# Output.net
KiCad netlist of a schematic drawn in Altium Designer
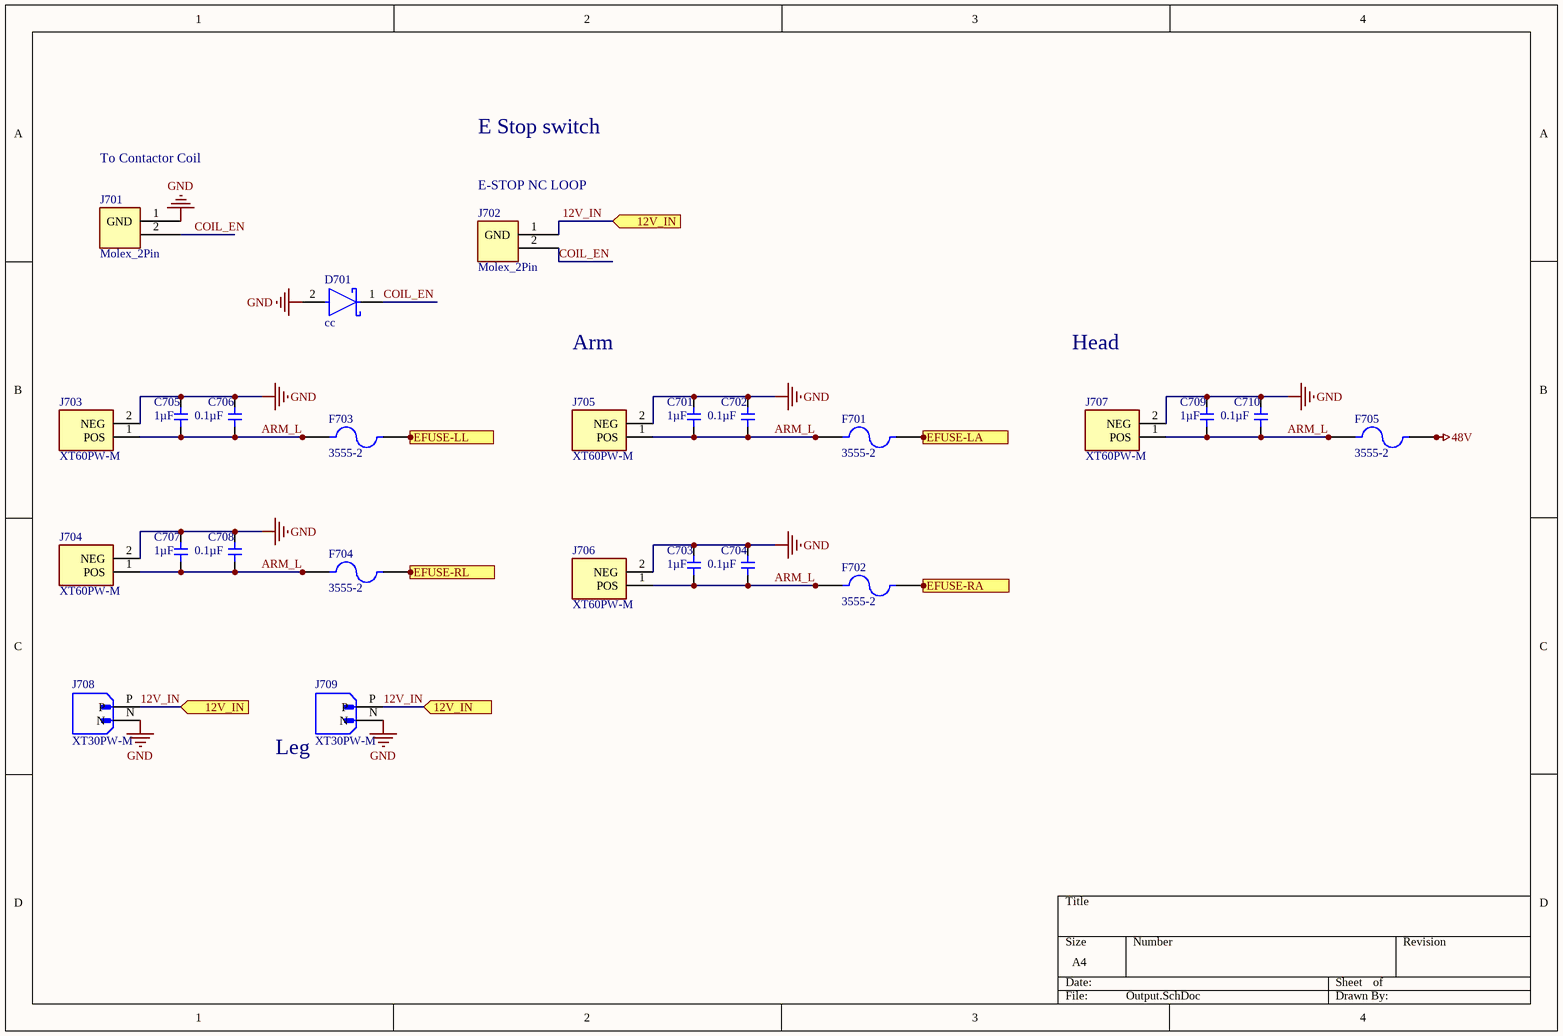
[diagram p0: Output.SchDoc]

(export (version "E")
  (design (tool "Eeschema 10.0.6"))
  (components
    (comp (ref "C701")
      (value "non-polar_Capacitor")
      (footprint "0805")
      (description "SMD type ceramic capacitor")
      (fields
        (field (name "VOLTAGE") "100V")
        (field (name "CAPACITANCE") "1µF")
        (field (name "SOURCE") "robit_passive.SchLib")
      )
      (libsource (lib "robit circuit") (part "Capacitor"))
    )
    (comp (ref "C702")
      (value "non-polar_Capacitor")
      (footprint "0603")
      (description "SMD type ceramic capacitor")
      (fields
        (field (name "VOLTAGE") "100V")
        (field (name "CAPACITANCE") "0.1µF")
        (field (name "SOURCE") "robit_passive.SchLib")
      )
      (libsource (lib "robit circuit") (part "Capacitor"))
    )
    (comp (ref "C703")
      (value "non-polar_Capacitor")
      (footprint "0805")
      (description "SMD type ceramic capacitor")
      (fields
        (field (name "VOLTAGE") "100V")
        (field (name "CAPACITANCE") "1µF")
        (field (name "SOURCE") "robit_passive.SchLib")
      )
      (libsource (lib "robit circuit") (part "Capacitor"))
    )
    (comp (ref "C704")
      (value "non-polar_Capacitor")
      (footprint "0603")
      (description "SMD type ceramic capacitor")
      (fields
        (field (name "VOLTAGE") "100V")
        (field (name "CAPACITANCE") "0.1µF")
        (field (name "SOURCE") "robit_passive.SchLib")
      )
      (libsource (lib "robit circuit") (part "Capacitor"))
    )
    (comp (ref "C705")
      (value "non-polar_Capacitor")
      (footprint "0805")
      (description "SMD type ceramic capacitor")
      (fields
        (field (name "VOLTAGE") "100V")
        (field (name "CAPACITANCE") "1µF")
        (field (name "SOURCE") "robit_passive.SchLib")
      )
      (libsource (lib "robit circuit") (part "Capacitor"))
    )
    (comp (ref "C706")
      (value "non-polar_Capacitor")
      (footprint "0603")
      (description "SMD type ceramic capacitor")
      (fields
        (field (name "VOLTAGE") "100V")
        (field (name "CAPACITANCE") "0.1µF")
        (field (name "SOURCE") "robit_passive.SchLib")
      )
      (libsource (lib "robit circuit") (part "Capacitor"))
    )
    (comp (ref "C707")
      (value "non-polar_Capacitor")
      (footprint "0805")
      (description "SMD type ceramic capacitor")
      (fields
        (field (name "VOLTAGE") "100V")
        (field (name "CAPACITANCE") "1µF")
        (field (name "SOURCE") "robit_passive.SchLib")
      )
      (libsource (lib "robit circuit") (part "Capacitor"))
    )
    (comp (ref "C708")
      (value "non-polar_Capacitor")
      (footprint "0603")
      (description "SMD type ceramic capacitor")
      (fields
        (field (name "VOLTAGE") "100V")
        (field (name "CAPACITANCE") "0.1µF")
        (field (name "SOURCE") "robit_passive.SchLib")
      )
      (libsource (lib "robit circuit") (part "Capacitor"))
    )
    (comp (ref "C709")
      (value "non-polar_Capacitor")
      (footprint "0805")
      (description "SMD type ceramic capacitor")
      (fields
        (field (name "VOLTAGE") "100V")
        (field (name "CAPACITANCE") "1µF")
        (field (name "SOURCE") "robit_passive.SchLib")
      )
      (libsource (lib "robit circuit") (part "Capacitor"))
    )
    (comp (ref "C710")
      (value "non-polar_Capacitor")
      (footprint "0603")
      (description "SMD type ceramic capacitor")
      (fields
        (field (name "VOLTAGE") "100V")
        (field (name "CAPACITANCE") "0.1µF")
        (field (name "SOURCE") "robit_passive.SchLib")
      )
      (libsource (lib "robit circuit") (part "Capacitor"))
    )
    (comp (ref "D701")
      (value "cc")
      (footprint "FP-403A-03-MFG")
      (description "Rectifier Diode, Schottky, 1 Phase, 1 Element, 5A, 100V V(RRM), Silicon")
      (libsource (lib "robit circuit") (part "1d6ec82d83fb6aee721767c19dac4b9"))
    )
    (comp (ref "F701")
      (value "3555-2")
      (footprint "FUSE_3555-2")
      (fields (field (name "MF") "Keystone Electronics"))
      (libsource (lib "3555-2 (1)") (part "3555-2"))
    )
    (comp (ref "F702")
      (value "3555-2")
      (footprint "FUSE_3555-2")
      (fields (field (name "MF") "Keystone Electronics"))
      (libsource (lib "3555-2 (1)") (part "3555-2"))
    )
    (comp (ref "F703")
      (value "3555-2")
      (footprint "FUSE_3555-2")
      (fields (field (name "MF") "Keystone Electronics"))
      (libsource (lib "3555-2 (1)") (part "3555-2"))
    )
    (comp (ref "F704")
      (value "3555-2")
      (footprint "FUSE_3555-2")
      (fields (field (name "MF") "Keystone Electronics"))
      (libsource (lib "3555-2 (1)") (part "3555-2"))
    )
    (comp (ref "F705")
      (value "3555-2")
      (footprint "FUSE_3555-2")
      (fields (field (name "MF") "Keystone Electronics"))
      (libsource (lib "3555-2 (1)") (part "3555-2"))
    )
    (comp (ref "J701")
      (value "Molex_2Pin")
      (footprint "MOLEX_2PIN")
      (description "Molex 2Pin Connector")
      (fields (field (name "SOURCE") "robit_connector.SchLib"))
      (libsource (lib "robit circuit") (part "Molex_2Pin"))
    )
    (comp (ref "J702")
      (value "Molex_2Pin")
      (footprint "MOLEX_2PIN")
      (description "Molex 2Pin Connector")
      (fields (field (name "SOURCE") "robit_connector.SchLib"))
      (libsource (lib "robit circuit") (part "Molex_2Pin"))
    )
    (comp (ref "J703")
      (value "XT60PW-M")
      (footprint "XT60PW-M")
      (description "Socket, DC supply, male, PIN: 2")
      (fields (field (name "MF") "AMASS") (field (name "SOURCE") "robit_connector.SchLib"))
      (libsource (lib "robit circuit") (part "XT60PW-M"))
    )
    (comp (ref "J704")
      (value "XT60PW-M")
      (footprint "XT60PW-M")
      (description "Socket, DC supply, male, PIN: 2")
      (fields (field (name "MF") "AMASS") (field (name "SOURCE") "robit_connector.SchLib"))
      (libsource (lib "robit circuit") (part "XT60PW-M"))
    )
    (comp (ref "J705")
      (value "XT60PW-M")
      (footprint "XT60PW-M")
      (description "Socket, DC supply, male, PIN: 2")
      (fields (field (name "MF") "AMASS") (field (name "SOURCE") "robit_connector.SchLib"))
      (libsource (lib "robit circuit") (part "XT60PW-M"))
    )
    (comp (ref "J706")
      (value "XT60PW-M")
      (footprint "XT60PW-M")
      (description "Socket, DC supply, male, PIN: 2")
      (fields (field (name "MF") "AMASS") (field (name "SOURCE") "robit_connector.SchLib"))
      (libsource (lib "robit circuit") (part "XT60PW-M"))
    )
    (comp (ref "J707")
      (value "XT60PW-M")
      (footprint "XT60PW-M")
      (description "Socket, DC supply, male, PIN: 2")
      (fields (field (name "MF") "AMASS") (field (name "SOURCE") "robit_connector.SchLib"))
      (libsource (lib "robit circuit") (part "XT60PW-M"))
    )
    (comp (ref "J708")
      (value "XT30PW-M")
      (footprint "AMASS_XT30PW-M")
      (description "Socket; DC supply; XT30; male; PIN: 2; on PCBs; THT; Colour: yellow")
      (fields (field (name "MF") "AMASS"))
      (libsource (lib "robit circuit") (part "XT30PW-M"))
    )
    (comp (ref "J709")
      (value "XT30PW-M")
      (footprint "AMASS_XT30PW-M")
      (description "Socket; DC supply; XT30; male; PIN: 2; on PCBs; THT; Colour: yellow")
      (fields (field (name "MF") "AMASS"))
      (libsource (lib "robit circuit") (part "XT30PW-M"))
    )
  )
  (nets
    (net (code "1") (name "/12V_IN") (class "Default")
      (node (ref "J702") (pin "1") (pinfunction "GND_1") (pintype "passive"))
      (node (ref "J708") (pin "P") (pinfunction "P_P") (pintype "power_in"))
      (node (ref "J709") (pin "P") (pinfunction "P_P") (pintype "power_in"))
    )
    (net (code "2") (name "/ARM_L") (class "Default")
      (node (ref "C701") (pin "1") (pinfunction "1_1") (pintype "passive"))
      (node (ref "C702") (pin "1") (pinfunction "1_1") (pintype "passive"))
      (node (ref "C703") (pin "1") (pinfunction "1_1") (pintype "passive"))
      (node (ref "C704") (pin "1") (pinfunction "1_1") (pintype "passive"))
      (node (ref "C705") (pin "1") (pinfunction "1_1") (pintype "passive"))
      (node (ref "C706") (pin "1") (pinfunction "1_1") (pintype "passive"))
      (node (ref "C707") (pin "1") (pinfunction "1_1") (pintype "passive"))
      (node (ref "C708") (pin "1") (pinfunction "1_1") (pintype "passive"))
      (node (ref "C709") (pin "1") (pinfunction "1_1") (pintype "passive"))
      (node (ref "C710") (pin "1") (pinfunction "1_1") (pintype "passive"))
      (node (ref "F701") (pin "1_1") (pinfunction "1_1_1") (pintype "passive"))
      (node (ref "F701") (pin "1_2") (pinfunction "1_1_2") (pintype "passive"))
      (node (ref "F702") (pin "1_1") (pinfunction "1_1_1") (pintype "passive"))
      (node (ref "F702") (pin "1_2") (pinfunction "1_1_2") (pintype "passive"))
      (node (ref "F703") (pin "1_1") (pinfunction "1_1_1") (pintype "passive"))
      (node (ref "F703") (pin "1_2") (pinfunction "1_1_2") (pintype "passive"))
      (node (ref "F704") (pin "1_1") (pinfunction "1_1_1") (pintype "passive"))
      (node (ref "F704") (pin "1_2") (pinfunction "1_1_2") (pintype "passive"))
      (node (ref "F705") (pin "1_1") (pinfunction "1_1_1") (pintype "passive"))
      (node (ref "F705") (pin "1_2") (pinfunction "1_1_2") (pintype "passive"))
      (node (ref "J703") (pin "1") (pinfunction "POS_1") (pintype "passive"))
      (node (ref "J704") (pin "1") (pinfunction "POS_1") (pintype "passive"))
      (node (ref "J705") (pin "1") (pinfunction "POS_1") (pintype "passive"))
      (node (ref "J706") (pin "1") (pinfunction "POS_1") (pintype "passive"))
      (node (ref "J707") (pin "1") (pinfunction "POS_1") (pintype "passive"))
    )
    (net (code "3") (name "/COIL_EN") (class "Default")
      (node (ref "D701") (pin "1") (pinfunction "C_1") (pintype "passive"))
      (node (ref "J701") (pin "2") (pintype "passive"))
      (node (ref "J702") (pin "2") (pintype "passive"))
    )
    (net (code "4") (name "/EFUSE-LA") (class "Default")
      (node (ref "F701") (pin "2_1") (pinfunction "2_2_1") (pintype "passive"))
      (node (ref "F701") (pin "2_2") (pinfunction "2_2_2") (pintype "passive"))
    )
    (net (code "5") (name "/EFUSE-LL") (class "Default")
      (node (ref "F703") (pin "2_1") (pinfunction "2_2_1") (pintype "passive"))
      (node (ref "F703") (pin "2_2") (pinfunction "2_2_2") (pintype "passive"))
    )
    (net (code "6") (name "/EFUSE-RA") (class "Default")
      (node (ref "F702") (pin "2_1") (pinfunction "2_2_1") (pintype "passive"))
      (node (ref "F702") (pin "2_2") (pinfunction "2_2_2") (pintype "passive"))
    )
    (net (code "7") (name "/EFUSE-RL") (class "Default")
      (node (ref "F704") (pin "2_1") (pinfunction "2_2_1") (pintype "passive"))
      (node (ref "F704") (pin "2_2") (pinfunction "2_2_2") (pintype "passive"))
    )
    (net (code "8") (name "48V") (class "Default")
      (node (ref "F705") (pin "2_1") (pinfunction "2_2_1") (pintype "passive"))
      (node (ref "F705") (pin "2_2") (pinfunction "2_2_2") (pintype "passive"))
    )
    (net (code "9") (name "GND") (class "Default")
      (node (ref "C701") (pin "2") (pinfunction "2_2") (pintype "passive"))
      (node (ref "C702") (pin "2") (pinfunction "2_2") (pintype "passive"))
      (node (ref "C703") (pin "2") (pinfunction "2_2") (pintype "passive"))
      (node (ref "C704") (pin "2") (pinfunction "2_2") (pintype "passive"))
      (node (ref "C705") (pin "2") (pinfunction "2_2") (pintype "passive"))
      (node (ref "C706") (pin "2") (pinfunction "2_2") (pintype "passive"))
      (node (ref "C707") (pin "2") (pinfunction "2_2") (pintype "passive"))
      (node (ref "C708") (pin "2") (pinfunction "2_2") (pintype "passive"))
      (node (ref "C709") (pin "2") (pinfunction "2_2") (pintype "passive"))
      (node (ref "C710") (pin "2") (pinfunction "2_2") (pintype "passive"))
      (node (ref "D701") (pin "2") (pinfunction "A_2") (pintype "passive"))
      (node (ref "J701") (pin "1") (pinfunction "GND_1") (pintype "passive"))
      (node (ref "J703") (pin "2") (pinfunction "NEG_2") (pintype "passive"))
      (node (ref "J704") (pin "2") (pinfunction "NEG_2") (pintype "passive"))
      (node (ref "J705") (pin "2") (pinfunction "NEG_2") (pintype "passive"))
      (node (ref "J706") (pin "2") (pinfunction "NEG_2") (pintype "passive"))
      (node (ref "J707") (pin "2") (pinfunction "NEG_2") (pintype "passive"))
      (node (ref "J708") (pin "N") (pinfunction "N_N") (pintype "power_in"))
      (node (ref "J709") (pin "N") (pinfunction "N_N") (pintype "power_in"))
    )
  )
)
